# LCD_PWR.net
KiCad netlist of a schematic drawn in Altium Designer
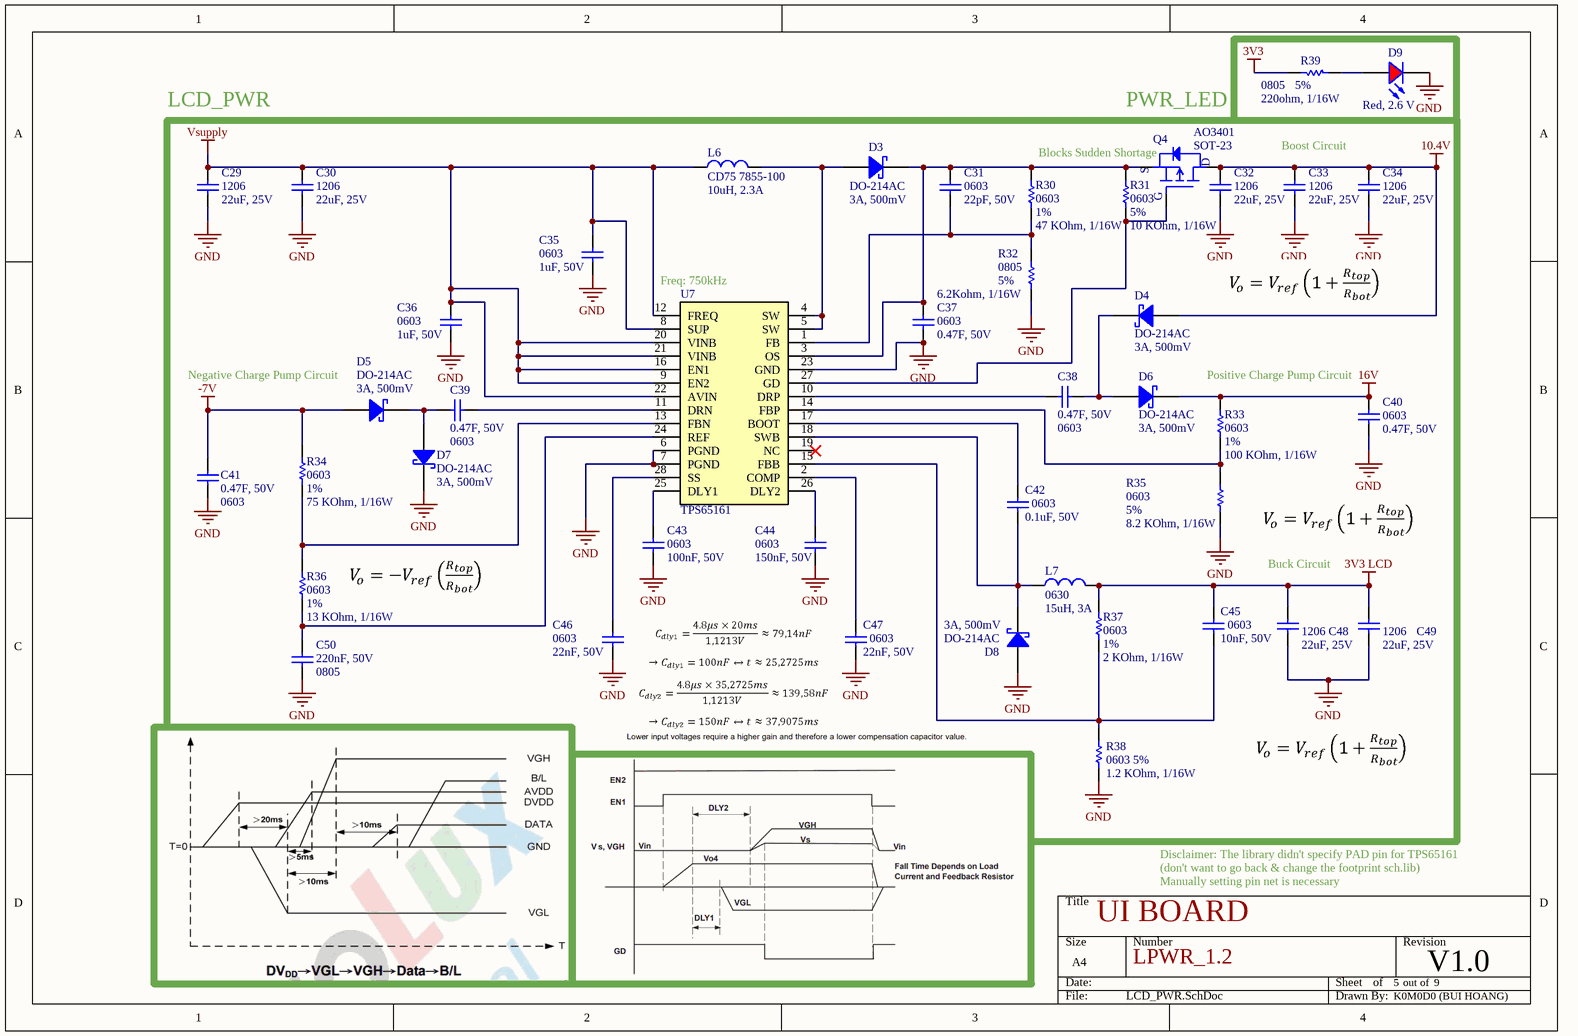
[diagram p0: LCD_PWR.SchDoc]

(export (version "E")
  (design (tool "Eeschema 10.0.6"))
  (components
    (comp (ref "C29")
      (value "22uF, 25V")
      (footprint "C_1206")
      (description "CAP_1206")
      (fields (field (name "PACKAGE") "1206"))
      (libsource (lib "DisplayLib") (part "CAP_1206"))
    )
    (comp (ref "C30")
      (value "22uF, 25V")
      (footprint "C_1206")
      (description "CAP_1206")
      (fields (field (name "PACKAGE") "1206"))
      (libsource (lib "DisplayLib") (part "CAP_1206"))
    )
    (comp (ref "C31")
      (value "22pF, 50V")
      (footprint "C_0603")
      (description "CAP_0603")
      (fields (field (name "PACKAGE") "0603"))
      (libsource (lib "DisplayLib") (part "CAP_0603"))
    )
    (comp (ref "C32")
      (value "22uF, 25V")
      (footprint "C_1206")
      (description "CAP_1206")
      (fields (field (name "PACKAGE") "1206"))
      (libsource (lib "DisplayLib") (part "CAP_1206"))
    )
    (comp (ref "C33")
      (value "22uF, 25V")
      (footprint "C_1206")
      (description "CAP_1206")
      (fields (field (name "PACKAGE") "1206"))
      (libsource (lib "DisplayLib") (part "CAP_1206"))
    )
    (comp (ref "C34")
      (value "22uF, 25V")
      (footprint "C_1206")
      (description "CAP_1206")
      (fields (field (name "PACKAGE") "1206"))
      (libsource (lib "DisplayLib") (part "CAP_1206"))
    )
    (comp (ref "C35")
      (value "1uF, 50V")
      (footprint "C_0603")
      (description "CAP_0603")
      (fields (field (name "PACKAGE") "0603"))
      (libsource (lib "DisplayLib") (part "CAP_0603"))
    )
    (comp (ref "C36")
      (value "1uF, 50V")
      (footprint "C_0603")
      (description "CAP_0603")
      (fields (field (name "PACKAGE") "0603"))
      (libsource (lib "DisplayLib") (part "CAP_0603"))
    )
    (comp (ref "C37")
      (value "0.47F, 50V")
      (footprint "C_0603")
      (description "CAP_0603")
      (fields (field (name "PACKAGE") "0603"))
      (libsource (lib "DisplayLib") (part "CAP_0603"))
    )
    (comp (ref "C38")
      (value "0.47F, 50V")
      (footprint "C_0603")
      (description "CAP_0603")
      (fields (field (name "PACKAGE") "0603"))
      (libsource (lib "DisplayLib") (part "CAP_0603"))
    )
    (comp (ref "C39")
      (value "0.47F, 50V")
      (footprint "C_0603")
      (description "CAP_0603")
      (fields (field (name "PACKAGE") "0603"))
      (libsource (lib "DisplayLib") (part "CAP_0603"))
    )
    (comp (ref "C40")
      (value "0.47F, 50V")
      (footprint "C_0603")
      (description "CAP_0603")
      (fields (field (name "PACKAGE") "0603"))
      (libsource (lib "DisplayLib") (part "CAP_0603"))
    )
    (comp (ref "C41")
      (value "0.47F, 50V")
      (footprint "C_0603")
      (description "CAP_0603")
      (fields (field (name "PACKAGE") "0603"))
      (libsource (lib "DisplayLib") (part "CAP_0603"))
    )
    (comp (ref "C42")
      (value "0.1uF, 50V")
      (footprint "C_0603")
      (description "CAP_0603")
      (fields (field (name "PACKAGE") "0603"))
      (libsource (lib "DisplayLib") (part "CAP_0603"))
    )
    (comp (ref "C43")
      (value "100nF, 50V")
      (footprint "C_0603")
      (description "CAP_0603")
      (fields (field (name "PACKAGE") "0603"))
      (libsource (lib "DisplayLib") (part "CAP_0603"))
    )
    (comp (ref "C44")
      (value "150nF, 50V")
      (footprint "C_0603")
      (description "CAP_0603")
      (fields (field (name "PACKAGE") "0603"))
      (libsource (lib "DisplayLib") (part "CAP_0603"))
    )
    (comp (ref "C45")
      (value "10nF, 50V")
      (footprint "C_0603")
      (description "CAP_0603")
      (fields (field (name "PACKAGE") "0603"))
      (libsource (lib "DisplayLib") (part "CAP_0603"))
    )
    (comp (ref "C46")
      (value "22nF, 50V")
      (footprint "C_0603")
      (description "CAP_0603")
      (fields (field (name "PACKAGE") "0603"))
      (libsource (lib "DisplayLib") (part "CAP_0603"))
    )
    (comp (ref "C47")
      (value "22nF, 50V")
      (footprint "C_0603")
      (description "CAP_0603")
      (fields (field (name "PACKAGE") "0603"))
      (libsource (lib "DisplayLib") (part "CAP_0603"))
    )
    (comp (ref "C48")
      (value "22uF, 25V")
      (footprint "C_1206")
      (description "CAP_1206")
      (fields (field (name "PACKAGE") "1206"))
      (libsource (lib "DisplayLib") (part "CAP_1206"))
    )
    (comp (ref "C49")
      (value "22uF, 25V")
      (footprint "C_1206")
      (description "CAP_1206")
      (fields (field (name "PACKAGE") "1206"))
      (libsource (lib "DisplayLib") (part "CAP_1206"))
    )
    (comp (ref "C50")
      (value "220nF, 50V")
      (footprint "C_0805")
      (description "CAP_0805")
      (fields (field (name "PACKAGE") "0805"))
      (libsource (lib "DisplayLib") (part "CAP_0805"))
    )
    (comp (ref "D3")
      (value "3A, 500mV")
      (footprint "PKG_SMA (DO-214AC)")
      (description "SS34")
      (fields (field (name "PACKAGE") "DO-214AC"))
      (libsource (lib "DisplayLib") (part "SCHOTTKY"))
    )
    (comp (ref "D4")
      (value "3A, 500mV")
      (footprint "PKG_SMA (DO-214AC)")
      (description "SS34")
      (fields (field (name "PACKAGE") "DO-214AC"))
      (libsource (lib "DisplayLib") (part "SCHOTTKY"))
    )
    (comp (ref "D5")
      (value "3A, 500mV")
      (footprint "PKG_SMA (DO-214AC)")
      (description "SS34")
      (fields (field (name "PACKAGE") "DO-214AC"))
      (libsource (lib "DisplayLib") (part "SCHOTTKY"))
    )
    (comp (ref "D6")
      (value "3A, 500mV")
      (footprint "PKG_SMA (DO-214AC)")
      (description "SS34")
      (fields (field (name "PACKAGE") "DO-214AC"))
      (libsource (lib "DisplayLib") (part "SCHOTTKY"))
    )
    (comp (ref "D7")
      (value "3A, 500mV")
      (footprint "PKG_SMA (DO-214AC)")
      (description "SS34")
      (fields (field (name "PACKAGE") "DO-214AC"))
      (libsource (lib "DisplayLib") (part "SCHOTTKY"))
    )
    (comp (ref "D8")
      (value "3A, 500mV")
      (footprint "PKG_SMA (DO-214AC)")
      (description "SS34")
      (fields (field (name "PACKAGE") "DO-214AC"))
      (libsource (lib "DisplayLib") (part "SCHOTTKY"))
    )
    (comp (ref "D9")
      (value "Red, 2.6 V")
      (footprint "LED_1206")
      (description "Red LED")
      (libsource (lib "DisplayLib") (part "RED"))
    )
    (comp (ref "L6")
      (value "10uH, 2.3A")
      (footprint "COIL_CDRH")
      (description "IN_CD104_100")
      (fields (field (name "PACKAGE") "CD75 7855-100"))
      (libsource (lib "DisplayLib") (part "IN_CD104_100"))
    )
    (comp (ref "L7")
      (value "15uH, 3A")
      (footprint "COIL_74")
      (description "IN_0630")
      (fields (field (name "PACKAGE") "0630"))
      (libsource (lib "DisplayLib") (part "IN_0630"))
    )
    (comp (ref "Q4")
      (value "AO3401")
      (footprint "PKG_SOT-23")
      (description "P-Channel 30 V 4A (Ta) 1.4W (Ta) Surface Mount SOT-23-3")
      (fields (field (name "PACKAGE") "SOT-23"))
      (libsource (lib "DisplayLib") (part "AO3401"))
    )
    (comp (ref "R30")
      (value "47 KOhm, 1/16W")
      (footprint "R_0603")
      (description "RES_0603")
      (fields (field (name "PACKAGE") "0603") (field (name "ACC") "1%"))
      (libsource (lib "DisplayLib") (part "RES_0603"))
    )
    (comp (ref "R31")
      (value "10 KOhm, 1/16W")
      (footprint "R_0603")
      (description "RES_0603")
      (fields (field (name "PACKAGE") "0603") (field (name "ACC") "5%"))
      (libsource (lib "DisplayLib") (part "RES_0603"))
    )
    (comp (ref "R32")
      (value "6.2Kohm, 1/16W")
      (footprint "R_0805")
      (description "RES_0805")
      (fields (field (name "PACKAGE") "0805") (field (name "ACC") "5%"))
      (libsource (lib "DisplayLib") (part "RES_0805"))
    )
    (comp (ref "R33")
      (value "100 KOhm, 1/16W")
      (footprint "R_0603")
      (description "RES_0603")
      (fields (field (name "PACKAGE") "0603") (field (name "ACC") "1%"))
      (libsource (lib "DisplayLib") (part "RES_0603"))
    )
    (comp (ref "R34")
      (value "75 KOhm, 1/16W")
      (footprint "R_0603")
      (description "RES_0603")
      (fields (field (name "PACKAGE") "0603") (field (name "ACC") "1%"))
      (libsource (lib "DisplayLib") (part "RES_0603"))
    )
    (comp (ref "R35")
      (value "8.2 KOhm, 1/16W")
      (footprint "R_0603")
      (description "RES_0603")
      (fields (field (name "PACKAGE") "0603") (field (name "ACC") "5%"))
      (libsource (lib "DisplayLib") (part "RES_0603"))
    )
    (comp (ref "R36")
      (value "13 KOhm, 1/16W")
      (footprint "R_0603")
      (description "RES_0603")
      (fields (field (name "PACKAGE") "0603") (field (name "ACC") "1%"))
      (libsource (lib "DisplayLib") (part "RES_0603"))
    )
    (comp (ref "R37")
      (value "2 KOhm, 1/16W")
      (footprint "R_0603")
      (description "RES_0603")
      (fields (field (name "PACKAGE") "0603") (field (name "ACC") "1%"))
      (libsource (lib "DisplayLib") (part "RES_0603"))
    )
    (comp (ref "R38")
      (value "1.2 KOhm, 1/16W")
      (footprint "R_0603")
      (description "RES_0603")
      (fields (field (name "PACKAGE") "0603") (field (name "ACC") "5%"))
      (libsource (lib "DisplayLib") (part "RES_0603"))
    )
    (comp (ref "R39")
      (value "220ohm, 1/16W")
      (footprint "R_0805")
      (description "RES_0805")
      (fields (field (name "PACKAGE") "0805") (field (name "ACC") "5%"))
      (libsource (lib "DisplayLib") (part "RES_0805"))
    )
    (comp (ref "U7")
      (value "TPS65161")
      (footprint "PKG_HTSSOP-28")
      (description "BIAS POWER SUPPLY FOR TV AND MONITOR TFT LCD PANELS")
      (libsource (lib "DisplayLib") (part "TPS65161"))
    )
  )
  (nets
    (net (code "1") (name "-7V") (class "Default")
      (node (ref "C41") (pin "1") (pinfunction "1_1") (pintype "passive"))
      (node (ref "D5") (pin "2") (pinfunction "A_2") (pintype "passive"))
      (node (ref "R34") (pin "2") (pinfunction "2_2") (pintype "passive"))
    )
    (net (code "2") (name "3V3") (class "Default")
      (node (ref "R39") (pin "2") (pinfunction "2_2") (pintype "passive"))
    )
    (net (code "3") (name "3V3 LCD") (class "Default")
      (node (ref "C45") (pin "2") (pinfunction "2_2") (pintype "passive"))
      (node (ref "C48") (pin "2") (pinfunction "2_2") (pintype "passive"))
      (node (ref "C49") (pin "2") (pinfunction "2_2") (pintype "passive"))
      (node (ref "L7") (pin "2") (pinfunction "2_2") (pintype "passive"))
      (node (ref "R37") (pin "2") (pinfunction "2_2") (pintype "passive"))
    )
    (net (code "4") (name "10.4V") (class "Default")
      (node (ref "C32") (pin "2") (pinfunction "2_2") (pintype "passive"))
      (node (ref "C33") (pin "2") (pinfunction "2_2") (pintype "passive"))
      (node (ref "C34") (pin "2") (pinfunction "2_2") (pintype "passive"))
      (node (ref "D4") (pin "2") (pinfunction "A_2") (pintype "passive"))
      (node (ref "Q4") (pin "3") (pinfunction "D_3") (pintype "passive"))
    )
    (net (code "5") (name "16V") (class "Default")
      (node (ref "C40") (pin "2") (pinfunction "2_2") (pintype "passive"))
      (node (ref "D6") (pin "1") (pinfunction "K_1") (pintype "passive"))
      (node (ref "R33") (pin "2") (pinfunction "2_2") (pintype "passive"))
    )
    (net (code "6") (name "GND") (class "Default")
      (node (ref "C29") (pin "1") (pinfunction "1_1") (pintype "passive"))
      (node (ref "C30") (pin "1") (pinfunction "1_1") (pintype "passive"))
      (node (ref "C32") (pin "1") (pinfunction "1_1") (pintype "passive"))
      (node (ref "C33") (pin "1") (pinfunction "1_1") (pintype "passive"))
      (node (ref "C34") (pin "1") (pinfunction "1_1") (pintype "passive"))
      (node (ref "C35") (pin "1") (pinfunction "1_1") (pintype "passive"))
      (node (ref "C36") (pin "1") (pinfunction "1_1") (pintype "passive"))
      (node (ref "C37") (pin "1") (pinfunction "1_1") (pintype "passive"))
      (node (ref "C40") (pin "1") (pinfunction "1_1") (pintype "passive"))
      (node (ref "C41") (pin "2") (pinfunction "2_2") (pintype "passive"))
      (node (ref "C43") (pin "1") (pinfunction "1_1") (pintype "passive"))
      (node (ref "C44") (pin "1") (pinfunction "1_1") (pintype "passive"))
      (node (ref "C46") (pin "1") (pinfunction "1_1") (pintype "passive"))
      (node (ref "C47") (pin "1") (pinfunction "1_1") (pintype "passive"))
      (node (ref "C48") (pin "1") (pinfunction "1_1") (pintype "passive"))
      (node (ref "C49") (pin "1") (pinfunction "1_1") (pintype "passive"))
      (node (ref "C50") (pin "2") (pinfunction "2_2") (pintype "passive"))
      (node (ref "D7") (pin "1") (pinfunction "K_1") (pintype "passive"))
      (node (ref "D8") (pin "2") (pinfunction "A_2") (pintype "passive"))
      (node (ref "D9") (pin "1") (pinfunction "K_1") (pintype "passive"))
      (node (ref "R32") (pin "1") (pinfunction "1_1") (pintype "passive"))
      (node (ref "R35") (pin "1") (pinfunction "1_1") (pintype "passive"))
      (node (ref "R38") (pin "1") (pinfunction "1_1") (pintype "passive"))
      (node (ref "U7") (pin "23") (pinfunction "GND_23") (pintype "passive"))
      (node (ref "U7") (pin "6") (pinfunction "PGND_6") (pintype "passive"))
      (node (ref "U7") (pin "7") (pinfunction "PGND_7") (pintype "passive"))
    )
    (net (code "7") (name "Net-(D3-A)") (class "Default")
      (node (ref "D3") (pin "2") (pinfunction "A_2") (pintype "passive"))
      (node (ref "L6") (pin "2") (pinfunction "2_2") (pintype "passive"))
      (node (ref "U7") (pin "4") (pinfunction "SW_4") (pintype "passive"))
      (node (ref "U7") (pin "5") (pinfunction "SW_5") (pintype "passive"))
    )
    (net (code "8") (name "Net-(D3-K)") (class "Default")
      (node (ref "C31") (pin "2") (pinfunction "2_2") (pintype "passive"))
      (node (ref "C37") (pin "2") (pinfunction "2_2") (pintype "passive"))
      (node (ref "D3") (pin "1") (pinfunction "K_1") (pintype "passive"))
      (node (ref "Q4") (pin "2") (pinfunction "S_2") (pintype "passive"))
      (node (ref "R30") (pin "2") (pinfunction "2_2") (pintype "passive"))
      (node (ref "R31") (pin "2") (pinfunction "2_2") (pintype "passive"))
      (node (ref "U7") (pin "3") (pinfunction "OS_3") (pintype "passive"))
    )
    (net (code "9") (name "Net-(D4-K)") (class "Default")
      (node (ref "C38") (pin "1") (pinfunction "1_1") (pintype "passive"))
      (node (ref "D4") (pin "1") (pinfunction "K_1") (pintype "passive"))
      (node (ref "D6") (pin "2") (pinfunction "A_2") (pintype "passive"))
    )
    (net (code "10") (name "Net-(D5-K)") (class "Default")
      (node (ref "C39") (pin "2") (pinfunction "2_2") (pintype "passive"))
      (node (ref "D5") (pin "1") (pinfunction "K_1") (pintype "passive"))
      (node (ref "D7") (pin "2") (pinfunction "A_2") (pintype "passive"))
    )
    (net (code "11") (name "Net-(D8-K)") (class "Default")
      (node (ref "C42") (pin "1") (pinfunction "1_1") (pintype "passive"))
      (node (ref "D8") (pin "1") (pinfunction "K_1") (pintype "passive"))
      (node (ref "L7") (pin "1") (pinfunction "1_1") (pintype "passive"))
      (node (ref "U7") (pin "18") (pinfunction "SWB_18") (pintype "passive"))
    )
    (net (code "12") (name "Net-(D9-A)") (class "Default")
      (node (ref "D9") (pin "2") (pinfunction "A_2") (pintype "passive"))
      (node (ref "R39") (pin "1") (pinfunction "1_1") (pintype "passive"))
    )
    (net (code "13") (name "Net-(Q4-G)") (class "Default")
      (node (ref "Q4") (pin "1") (pinfunction "G_1") (pintype "passive"))
      (node (ref "R31") (pin "1") (pinfunction "1_1") (pintype "passive"))
      (node (ref "U7") (pin "27") (pinfunction "GD_27") (pintype "passive"))
    )
    (net (code "14") (name "Net-(U7-BOOT)") (class "Default")
      (node (ref "C42") (pin "2") (pinfunction "2_2") (pintype "passive"))
      (node (ref "U7") (pin "17") (pinfunction "BOOT_17") (pintype "passive"))
    )
    (net (code "15") (name "Net-(U7-COMP)") (class "Default")
      (node (ref "C47") (pin "2") (pinfunction "2_2") (pintype "passive"))
      (node (ref "U7") (pin "2") (pinfunction "COMP_2") (pintype "passive"))
    )
    (net (code "16") (name "Net-(U7-DLY1)") (class "Default")
      (node (ref "C43") (pin "2") (pinfunction "2_2") (pintype "passive"))
      (node (ref "U7") (pin "25") (pinfunction "DLY1_25") (pintype "passive"))
    )
    (net (code "17") (name "Net-(U7-DLY2)") (class "Default")
      (node (ref "C44") (pin "2") (pinfunction "2_2") (pintype "passive"))
      (node (ref "U7") (pin "26") (pinfunction "DLY2_26") (pintype "passive"))
    )
    (net (code "18") (name "Net-(U7-DRN)") (class "Default")
      (node (ref "C39") (pin "1") (pinfunction "1_1") (pintype "passive"))
      (node (ref "U7") (pin "11") (pinfunction "DRN_11") (pintype "passive"))
    )
    (net (code "19") (name "Net-(U7-DRP)") (class "Default")
      (node (ref "C38") (pin "2") (pinfunction "2_2") (pintype "passive"))
      (node (ref "U7") (pin "10") (pinfunction "DRP_10") (pintype "passive"))
    )
    (net (code "20") (name "Net-(U7-FB)") (class "Default")
      (node (ref "C31") (pin "1") (pinfunction "1_1") (pintype "passive"))
      (node (ref "R30") (pin "1") (pinfunction "1_1") (pintype "passive"))
      (node (ref "R32") (pin "2") (pinfunction "2_2") (pintype "passive"))
      (node (ref "U7") (pin "1") (pinfunction "FB_1") (pintype "passive"))
    )
    (net (code "21") (name "Net-(U7-FBB)") (class "Default")
      (node (ref "C45") (pin "1") (pinfunction "1_1") (pintype "passive"))
      (node (ref "R37") (pin "1") (pinfunction "1_1") (pintype "passive"))
      (node (ref "R38") (pin "2") (pinfunction "2_2") (pintype "passive"))
      (node (ref "U7") (pin "15") (pinfunction "FBB_15") (pintype "passive"))
    )
    (net (code "22") (name "Net-(U7-FBN)") (class "Default")
      (node (ref "R34") (pin "1") (pinfunction "1_1") (pintype "passive"))
      (node (ref "R36") (pin "2") (pinfunction "2_2") (pintype "passive"))
      (node (ref "U7") (pin "13") (pinfunction "FBN_13") (pintype "passive"))
    )
    (net (code "23") (name "Net-(U7-FBP)") (class "Default")
      (node (ref "R33") (pin "1") (pinfunction "1_1") (pintype "passive"))
      (node (ref "R35") (pin "2") (pinfunction "2_2") (pintype "passive"))
      (node (ref "U7") (pin "14") (pinfunction "FBP_14") (pintype "passive"))
    )
    (net (code "24") (name "Net-(U7-REF)") (class "Default")
      (node (ref "C50") (pin "1") (pinfunction "1_1") (pintype "passive"))
      (node (ref "R36") (pin "1") (pinfunction "1_1") (pintype "passive"))
      (node (ref "U7") (pin "24") (pinfunction "REF_24") (pintype "passive"))
    )
    (net (code "25") (name "Net-(U7-SS)") (class "Default")
      (node (ref "C46") (pin "2") (pinfunction "2_2") (pintype "passive"))
      (node (ref "U7") (pin "28") (pinfunction "SS_28") (pintype "passive"))
    )
    (net (code "26") (name "Vsupply") (class "Default")
      (node (ref "C29") (pin "2") (pinfunction "2_2") (pintype "passive"))
      (node (ref "C30") (pin "2") (pinfunction "2_2") (pintype "passive"))
      (node (ref "C35") (pin "2") (pinfunction "2_2") (pintype "passive"))
      (node (ref "C36") (pin "2") (pinfunction "2_2") (pintype "passive"))
      (node (ref "L6") (pin "1") (pinfunction "1_1") (pintype "passive"))
      (node (ref "U7") (pin "12") (pinfunction "FREQ_12") (pintype "passive"))
      (node (ref "U7") (pin "16") (pinfunction "EN1_16") (pintype "passive"))
      (node (ref "U7") (pin "20") (pinfunction "VINB_20") (pintype "passive"))
      (node (ref "U7") (pin "21") (pinfunction "VINB_21") (pintype "passive"))
      (node (ref "U7") (pin "22") (pinfunction "AVIN_22") (pintype "passive"))
      (node (ref "U7") (pin "8") (pinfunction "SUP_8") (pintype "passive"))
      (node (ref "U7") (pin "9") (pinfunction "EN2_9") (pintype "passive"))
    )
    (net (code "27") (name "unconnected-(U7-NC-Pad19)") (class "Default")
      (node (ref "U7") (pin "19") (pinfunction "NC_19") (pintype "passive+no_connect"))
    )
  )
)
